# ac-control-schematic.net
KiCad netlist of a schematic drawn in Altium Designer
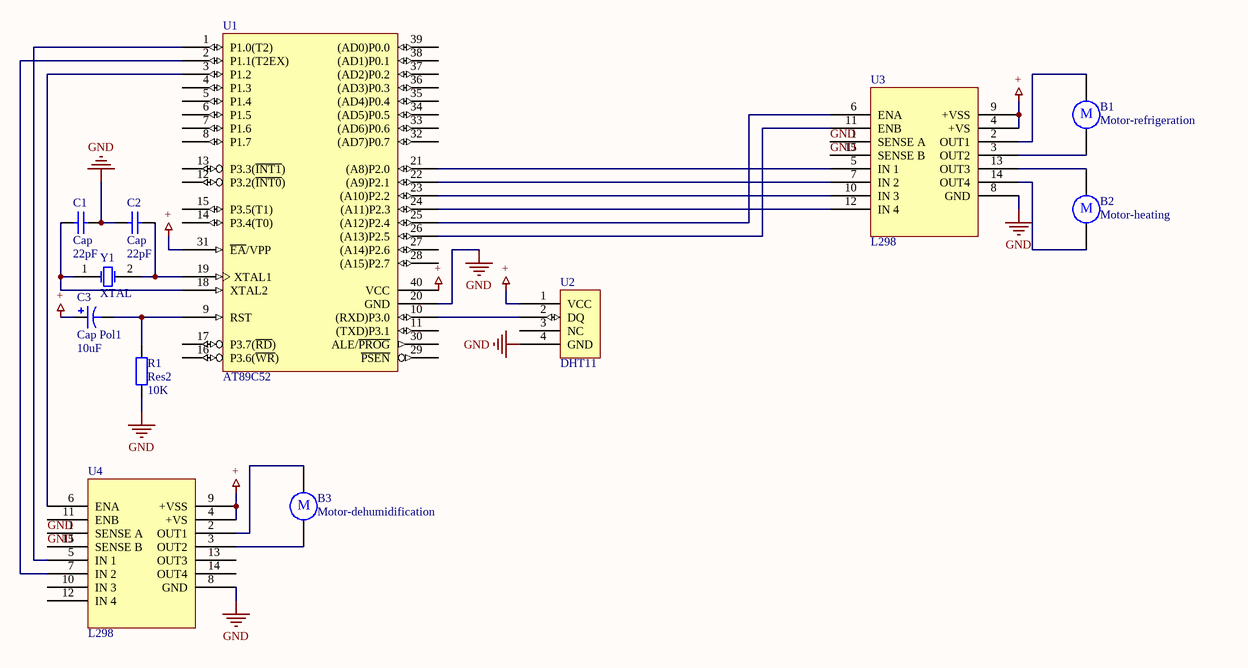
[diagram p0: ac-control-schematic.SchDoc]

(export (version "E")
  (design (tool "Eeschema 10.0.6"))
  (components
    (comp (ref "B1")
      (value "Motor-refrigeration")
      (footprint "RB5-10.5")
      (description "Motor, General Kind")
      (fields (field (name "PUBLISHER") "Altium Limited"))
      (libsource (lib "Miscellaneous Devices") (part "Motor"))
    )
    (comp (ref "B2")
      (value "Motor-heating")
      (footprint "RB5-10.5")
      (description "Motor, General Kind")
      (fields (field (name "PUBLISHER") "Altium Limited"))
      (libsource (lib "Miscellaneous Devices") (part "Motor"))
    )
    (comp (ref "B3")
      (value "Motor-dehumidification")
      (footprint "RB5-10.5")
      (description "Motor, General Kind")
      (fields (field (name "PUBLISHER") "Altium Limited"))
      (libsource (lib "Miscellaneous Devices") (part "Motor"))
    )
    (comp (ref "C1")
      (value "Cap")
      (footprint "RAD-0.3")
      (description "Capacitor")
      (fields (field (name "ALTIUM_VALUE") "22pF") (field (name "PUBLISHER") "Altium Limited"))
      (libsource (lib "Miscellaneous Devices") (part "Cap"))
    )
    (comp (ref "C2")
      (value "Cap")
      (footprint "RAD-0.3")
      (description "Capacitor")
      (fields (field (name "ALTIUM_VALUE") "22pF") (field (name "PUBLISHER") "Altium Limited"))
      (libsource (lib "Miscellaneous Devices") (part "Cap"))
    )
    (comp (ref "C3")
      (value "Cap Pol1")
      (footprint "RB7.6-15")
      (description "Polarized Capacitor (Radial)")
      (fields (field (name "ALTIUM_VALUE") "10uF") (field (name "PUBLISHER") "Altium Limited"))
      (libsource (lib "Miscellaneous Devices") (part "Cap Pol1"))
    )
    (comp (ref "R1")
      (value "Res2")
      (footprint "AXIAL-0.4")
      (description "Resistor")
      (fields (field (name "ALTIUM_VALUE") "10K") (field (name "PUBLISHER") "Altium Limited"))
      (libsource (lib "Miscellaneous Devices") (part "Res2"))
    )
    (comp (ref "U1")
      (value "AT89C52")
      (footprint "DIP-40W")
      (description "8-Bit Microcontroller with 8K Flash ROM")
      (libsource (lib "Atmel Microcontroller 8051 Architecture") (part "AT89C52"))
    )
    (comp (ref "U2") (value "DHT11") (footprint "HDR1X4") (libsource (lib "DHT11") (part "Component_1")))
    (comp (ref "U3") (value "L298") (footprint "L298") (libsource (lib "KU1") (part "L298N")))
    (comp (ref "U4") (value "L298") (footprint "L298") (libsource (lib "KU1") (part "L298N")))
    (comp (ref "Y1")
      (value "XTAL")
      (footprint "R38")
      (description "Crystal Oscillator")
      (fields (field (name "PUBLISHER") "Altium Limited"))
      (libsource (lib "Miscellaneous Devices") (part "XTAL"))
    )
  )
  (nets
    (net (code "1") (name "+") (class "Default")
      (node (ref "C3") (pin "1") (pinfunction "1_1") (pintype "passive"))
      (node (ref "U1") (pin "31") (pinfunction "~{EA}/VPP_31") (pintype "input"))
      (node (ref "U1") (pin "40") (pinfunction "VCC_40") (pintype "power_in"))
      (node (ref "U2") (pin "1") (pinfunction "VCC_1") (pintype "power_in"))
      (node (ref "U3") (pin "4") (pinfunction "+VS_4") (pintype "passive"))
      (node (ref "U3") (pin "9") (pinfunction "+VSS_9") (pintype "passive"))
      (node (ref "U4") (pin "4") (pinfunction "+VS_4") (pintype "passive"))
      (node (ref "U4") (pin "9") (pinfunction "+VSS_9") (pintype "passive"))
    )
    (net (code "2") (name "GND") (class "Default")
      (node (ref "C1") (pin "2") (pinfunction "2_2") (pintype "passive"))
      (node (ref "C2") (pin "1") (pinfunction "1_1") (pintype "passive"))
      (node (ref "R1") (pin "1") (pinfunction "1_1") (pintype "passive"))
      (node (ref "U1") (pin "20") (pinfunction "GND_20") (pintype "power_in"))
      (node (ref "U2") (pin "4") (pinfunction "GND_4") (pintype "power_in"))
      (node (ref "U3") (pin "1") (pinfunction "SENSE_A_1") (pintype "passive"))
      (node (ref "U3") (pin "15") (pinfunction "SENSE_B_15") (pintype "passive"))
      (node (ref "U3") (pin "8") (pinfunction "GND_8") (pintype "passive"))
      (node (ref "U4") (pin "1") (pinfunction "SENSE_A_1") (pintype "passive"))
      (node (ref "U4") (pin "15") (pinfunction "SENSE_B_15") (pintype "passive"))
      (node (ref "U4") (pin "8") (pinfunction "GND_8") (pintype "passive"))
    )
    (net (code "3") (name "Net-(U1-(A8)P2.0)") (class "Default")
      (node (ref "U1") (pin "21") (pinfunction "(A8)P2.0_21") (pintype "bidirectional"))
      (node (ref "U3") (pin "5") (pinfunction "IN_1_5") (pintype "passive"))
    )
    (net (code "4") (name "Net-(U1-(A9)P2.1)") (class "Default")
      (node (ref "U1") (pin "22") (pinfunction "(A9)P2.1_22") (pintype "bidirectional"))
      (node (ref "U3") (pin "7") (pinfunction "IN_2_7") (pintype "passive"))
    )
    (net (code "5") (name "Net-(U1-(A10)P2.2)") (class "Default")
      (node (ref "U1") (pin "23") (pinfunction "(A10)P2.2_23") (pintype "bidirectional"))
      (node (ref "U3") (pin "10") (pinfunction "IN_3_10") (pintype "passive"))
    )
    (net (code "6") (name "Net-(U1-(A11)P2.3)") (class "Default")
      (node (ref "U1") (pin "24") (pinfunction "(A11)P2.3_24") (pintype "bidirectional"))
      (node (ref "U3") (pin "12") (pinfunction "IN_4_12") (pintype "passive"))
    )
    (net (code "7") (name "Net-(U1-(A12)P2.4)") (class "Default")
      (node (ref "U1") (pin "25") (pinfunction "(A12)P2.4_25") (pintype "bidirectional"))
      (node (ref "U3") (pin "6") (pinfunction "ENA_6") (pintype "passive"))
    )
    (net (code "8") (name "Net-(U1-(A13)P2.5)") (class "Default")
      (node (ref "U1") (pin "26") (pinfunction "(A13)P2.5_26") (pintype "bidirectional"))
      (node (ref "U3") (pin "11") (pinfunction "ENB_11") (pintype "passive"))
    )
    (net (code "9") (name "Net-(U1-(RXD)P3.0)") (class "Default")
      (node (ref "U1") (pin "10") (pinfunction "(RXD)P3.0_10") (pintype "bidirectional"))
      (node (ref "U2") (pin "2") (pinfunction "DQ_2") (pintype "bidirectional"))
    )
    (net (code "10") (name "Net-(U1-P1.0(T2))") (class "Default")
      (node (ref "U1") (pin "1") (pinfunction "P1.0(T2)_1") (pintype "bidirectional"))
      (node (ref "U4") (pin "5") (pinfunction "IN_1_5") (pintype "passive"))
    )
    (net (code "11") (name "Net-(U1-P1.1(T2EX))") (class "Default")
      (node (ref "U1") (pin "2") (pinfunction "P1.1(T2EX)_2") (pintype "bidirectional"))
      (node (ref "U4") (pin "7") (pinfunction "IN_2_7") (pintype "passive"))
    )
    (net (code "12") (name "Net-(U1-P1.2)") (class "Default")
      (node (ref "U1") (pin "3") (pinfunction "P1.2_3") (pintype "bidirectional"))
      (node (ref "U4") (pin "6") (pinfunction "ENA_6") (pintype "passive"))
    )
    (net (code "13") (name "Net-(U1-RST)") (class "Default")
      (node (ref "C3") (pin "2") (pinfunction "2_2") (pintype "passive"))
      (node (ref "R1") (pin "2") (pinfunction "2_2") (pintype "passive"))
      (node (ref "U1") (pin "9") (pinfunction "RST_9") (pintype "input"))
    )
    (net (code "14") (name "Net-(U1-XTAL1)") (class "Default")
      (node (ref "C2") (pin "2") (pinfunction "2_2") (pintype "passive"))
      (node (ref "U1") (pin "19") (pinfunction "XTAL1_19") (pintype "input"))
      (node (ref "Y1") (pin "2") (pinfunction "OSC2_2") (pintype "passive"))
    )
    (net (code "15") (name "Net-(U1-XTAL2)") (class "Default")
      (node (ref "C1") (pin "1") (pinfunction "1_1") (pintype "passive"))
      (node (ref "U1") (pin "18") (pinfunction "XTAL2_18") (pintype "input"))
      (node (ref "Y1") (pin "1") (pinfunction "OSC1_1") (pintype "passive"))
    )
    (net (code "16") (name "Net-(U3-OUT1)") (class "Default")
      (node (ref "B1") (pin "1") (pinfunction "1_1") (pintype "passive"))
      (node (ref "U3") (pin "2") (pinfunction "OUT1_2") (pintype "passive"))
    )
    (net (code "17") (name "Net-(U3-OUT2)") (class "Default")
      (node (ref "B1") (pin "2") (pinfunction "2_2") (pintype "passive"))
      (node (ref "U3") (pin "3") (pinfunction "OUT2_3") (pintype "passive"))
    )
    (net (code "18") (name "Net-(U3-OUT3)") (class "Default")
      (node (ref "B2") (pin "1") (pinfunction "1_1") (pintype "passive"))
      (node (ref "U3") (pin "13") (pinfunction "OUT3_13") (pintype "passive"))
    )
    (net (code "19") (name "Net-(U3-OUT4)") (class "Default")
      (node (ref "B2") (pin "2") (pinfunction "2_2") (pintype "passive"))
      (node (ref "U3") (pin "14") (pinfunction "OUT4_14") (pintype "passive"))
    )
    (net (code "20") (name "Net-(U4-OUT1)") (class "Default")
      (node (ref "B3") (pin "1") (pinfunction "1_1") (pintype "passive"))
      (node (ref "U4") (pin "2") (pinfunction "OUT1_2") (pintype "passive"))
    )
    (net (code "21") (name "Net-(U4-OUT2)") (class "Default")
      (node (ref "B3") (pin "2") (pinfunction "2_2") (pintype "passive"))
      (node (ref "U4") (pin "3") (pinfunction "OUT2_3") (pintype "passive"))
    )
    (net (code "22") (name "unconnected-(U1-(A14)P2.6-Pad27)") (class "Default")
      (node (ref "U1") (pin "27") (pinfunction "(A14)P2.6_27") (pintype "bidirectional"))
    )
    (net (code "23") (name "unconnected-(U1-(A15)P2.7-Pad28)") (class "Default")
      (node (ref "U1") (pin "28") (pinfunction "(A15)P2.7_28") (pintype "bidirectional"))
    )
    (net (code "24") (name "unconnected-(U1-(AD0)P0.0-Pad39)") (class "Default")
      (node (ref "U1") (pin "39") (pinfunction "(AD0)P0.0_39") (pintype "bidirectional"))
    )
    (net (code "25") (name "unconnected-(U1-(AD1)P0.1-Pad38)") (class "Default")
      (node (ref "U1") (pin "38") (pinfunction "(AD1)P0.1_38") (pintype "bidirectional"))
    )
    (net (code "26") (name "unconnected-(U1-(AD2)P0.2-Pad37)") (class "Default")
      (node (ref "U1") (pin "37") (pinfunction "(AD2)P0.2_37") (pintype "bidirectional"))
    )
    (net (code "27") (name "unconnected-(U1-(AD3)P0.3-Pad36)") (class "Default")
      (node (ref "U1") (pin "36") (pinfunction "(AD3)P0.3_36") (pintype "bidirectional"))
    )
    (net (code "28") (name "unconnected-(U1-(AD4)P0.4-Pad35)") (class "Default")
      (node (ref "U1") (pin "35") (pinfunction "(AD4)P0.4_35") (pintype "bidirectional"))
    )
    (net (code "29") (name "unconnected-(U1-(AD5)P0.5-Pad34)") (class "Default")
      (node (ref "U1") (pin "34") (pinfunction "(AD5)P0.5_34") (pintype "bidirectional"))
    )
    (net (code "30") (name "unconnected-(U1-(AD6)P0.6-Pad33)") (class "Default")
      (node (ref "U1") (pin "33") (pinfunction "(AD6)P0.6_33") (pintype "bidirectional"))
    )
    (net (code "31") (name "unconnected-(U1-(AD7)P0.7-Pad32)") (class "Default")
      (node (ref "U1") (pin "32") (pinfunction "(AD7)P0.7_32") (pintype "bidirectional"))
    )
    (net (code "32") (name "unconnected-(U1-(TXD)P3.1-Pad11)") (class "Default")
      (node (ref "U1") (pin "11") (pinfunction "(TXD)P3.1_11") (pintype "bidirectional"))
    )
    (net (code "33") (name "unconnected-(U1-ALE{slash}~{PROG}-Pad30)") (class "Default")
      (node (ref "U1") (pin "30") (pinfunction "ALE/~{PROG}_30") (pintype "output"))
    )
    (net (code "34") (name "unconnected-(U1-P1.3-Pad4)") (class "Default")
      (node (ref "U1") (pin "4") (pinfunction "P1.3_4") (pintype "bidirectional"))
    )
    (net (code "35") (name "unconnected-(U1-P1.4-Pad5)") (class "Default")
      (node (ref "U1") (pin "5") (pinfunction "P1.4_5") (pintype "bidirectional"))
    )
    (net (code "36") (name "unconnected-(U1-P1.5-Pad6)") (class "Default")
      (node (ref "U1") (pin "6") (pinfunction "P1.5_6") (pintype "bidirectional"))
    )
    (net (code "37") (name "unconnected-(U1-P1.6-Pad7)") (class "Default")
      (node (ref "U1") (pin "7") (pinfunction "P1.6_7") (pintype "bidirectional"))
    )
    (net (code "38") (name "unconnected-(U1-P1.7-Pad8)") (class "Default")
      (node (ref "U1") (pin "8") (pinfunction "P1.7_8") (pintype "bidirectional"))
    )
    (net (code "39") (name "unconnected-(U1-P3.2(~{INT0})-Pad12)") (class "Default")
      (node (ref "U1") (pin "12") (pinfunction "P3.2(~{INT0})_12") (pintype "bidirectional"))
    )
    (net (code "40") (name "unconnected-(U1-P3.3(~{INT1})-Pad13)") (class "Default")
      (node (ref "U1") (pin "13") (pinfunction "P3.3(~{INT1})_13") (pintype "bidirectional"))
    )
    (net (code "41") (name "unconnected-(U1-P3.4(T0)-Pad14)") (class "Default")
      (node (ref "U1") (pin "14") (pinfunction "P3.4(T0)_14") (pintype "bidirectional"))
    )
    (net (code "42") (name "unconnected-(U1-P3.5(T1)-Pad15)") (class "Default")
      (node (ref "U1") (pin "15") (pinfunction "P3.5(T1)_15") (pintype "bidirectional"))
    )
    (net (code "43") (name "unconnected-(U1-P3.6(~{WR})-Pad16)") (class "Default")
      (node (ref "U1") (pin "16") (pinfunction "P3.6(~{WR})_16") (pintype "bidirectional"))
    )
    (net (code "44") (name "unconnected-(U1-P3.7(~{RD})-Pad17)") (class "Default")
      (node (ref "U1") (pin "17") (pinfunction "P3.7(~{RD})_17") (pintype "bidirectional"))
    )
    (net (code "45") (name "unconnected-(U1-~{PSEN}-Pad29)") (class "Default")
      (node (ref "U1") (pin "29") (pinfunction "~{PSEN}_29") (pintype "output"))
    )
    (net (code "46") (name "unconnected-(U2-NC-Pad3)") (class "Default")
      (node (ref "U2") (pin "3") (pinfunction "NC_3") (pintype "passive"))
    )
    (net (code "47") (name "unconnected-(U4-ENB-Pad11)") (class "Default")
      (node (ref "U4") (pin "11") (pinfunction "ENB_11") (pintype "passive"))
    )
    (net (code "48") (name "unconnected-(U4-IN_3-Pad10)") (class "Default")
      (node (ref "U4") (pin "10") (pinfunction "IN_3_10") (pintype "passive"))
    )
    (net (code "49") (name "unconnected-(U4-IN_4-Pad12)") (class "Default")
      (node (ref "U4") (pin "12") (pinfunction "IN_4_12") (pintype "passive"))
    )
    (net (code "50") (name "unconnected-(U4-OUT3-Pad13)") (class "Default")
      (node (ref "U4") (pin "13") (pinfunction "OUT3_13") (pintype "passive"))
    )
    (net (code "51") (name "unconnected-(U4-OUT4-Pad14)") (class "Default")
      (node (ref "U4") (pin "14") (pinfunction "OUT4_14") (pintype "passive"))
    )
  )
)
